# 08_Target_Bd_Connector.net
KiCad netlist of a schematic drawn in Altium Designer
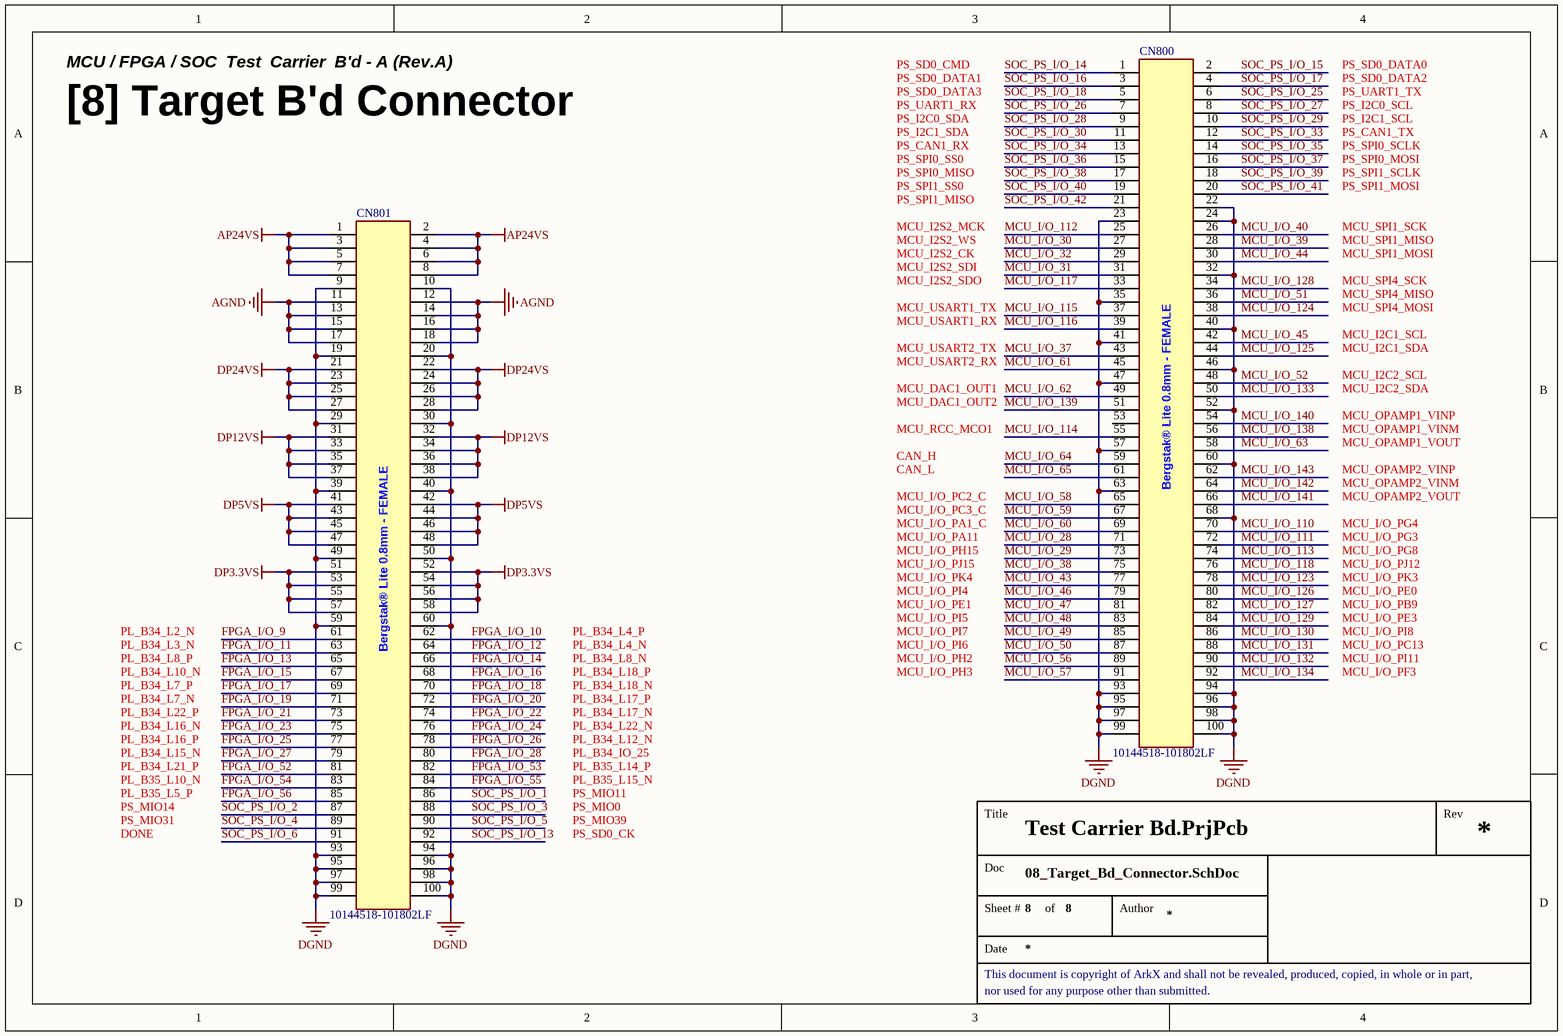
[diagram p0: 08_Target_Bd_Connector.SchDoc]

(export (version "E")
  (design (tool "Eeschema 10.0.6"))
  (components
    (comp (ref "CN800")
      (value "10144518-101802LF")
      (footprint "CON_BergStak-Lite(0.8mm)_FEMALE-100P(10144518-101802LF)_HandSolder")
      (libsource (lib "Arkx") (part "CON_BergStak-Lite(0.8mm)_FEMALE-100P(10144518-101802LF)"))
    )
    (comp (ref "CN801")
      (value "10144518-101802LF")
      (footprint "CON_BergStak-Lite(0.8mm)_FEMALE-100P(10144518-101802LF)_HandSolder")
      (libsource (lib "Arkx") (part "CON_BergStak-Lite(0.8mm)_FEMALE-100P(10144518-101802LF)"))
    )
  )
  (nets
    (net (code "1") (name "/FPGA_I{slash}O_9") (class "Default")
      (node (ref "CN801") (pin "61") (pinfunction "61_61") (pintype "passive"))
    )
    (net (code "2") (name "/FPGA_I{slash}O_10") (class "Default")
      (node (ref "CN801") (pin "62") (pinfunction "62_62") (pintype "passive"))
    )
    (net (code "3") (name "/FPGA_I{slash}O_11") (class "Default")
      (node (ref "CN801") (pin "63") (pinfunction "63_63") (pintype "passive"))
    )
    (net (code "4") (name "/FPGA_I{slash}O_12") (class "Default")
      (node (ref "CN801") (pin "64") (pinfunction "64_64") (pintype "passive"))
    )
    (net (code "5") (name "/FPGA_I{slash}O_13") (class "Default")
      (node (ref "CN801") (pin "65") (pinfunction "65_65") (pintype "passive"))
    )
    (net (code "6") (name "/FPGA_I{slash}O_14") (class "Default")
      (node (ref "CN801") (pin "66") (pinfunction "66_66") (pintype "passive"))
    )
    (net (code "7") (name "/FPGA_I{slash}O_15") (class "Default")
      (node (ref "CN801") (pin "67") (pinfunction "67_67") (pintype "passive"))
    )
    (net (code "8") (name "/FPGA_I{slash}O_16") (class "Default")
      (node (ref "CN801") (pin "68") (pinfunction "68_68") (pintype "passive"))
    )
    (net (code "9") (name "/FPGA_I{slash}O_17") (class "Default")
      (node (ref "CN801") (pin "69") (pinfunction "69_69") (pintype "passive"))
    )
    (net (code "10") (name "/FPGA_I{slash}O_18") (class "Default")
      (node (ref "CN801") (pin "70") (pinfunction "70_70") (pintype "passive"))
    )
    (net (code "11") (name "/FPGA_I{slash}O_19") (class "Default")
      (node (ref "CN801") (pin "71") (pinfunction "71_71") (pintype "passive"))
    )
    (net (code "12") (name "/FPGA_I{slash}O_20") (class "Default")
      (node (ref "CN801") (pin "72") (pinfunction "72_72") (pintype "passive"))
    )
    (net (code "13") (name "/FPGA_I{slash}O_21") (class "Default")
      (node (ref "CN801") (pin "73") (pinfunction "73_73") (pintype "passive"))
    )
    (net (code "14") (name "/FPGA_I{slash}O_22") (class "Default")
      (node (ref "CN801") (pin "74") (pinfunction "74_74") (pintype "passive"))
    )
    (net (code "15") (name "/FPGA_I{slash}O_23") (class "Default")
      (node (ref "CN801") (pin "75") (pinfunction "75_75") (pintype "passive"))
    )
    (net (code "16") (name "/FPGA_I{slash}O_24") (class "Default")
      (node (ref "CN801") (pin "76") (pinfunction "76_76") (pintype "passive"))
    )
    (net (code "17") (name "/FPGA_I{slash}O_25") (class "Default")
      (node (ref "CN801") (pin "77") (pinfunction "77_77") (pintype "passive"))
    )
    (net (code "18") (name "/FPGA_I{slash}O_26") (class "Default")
      (node (ref "CN801") (pin "78") (pinfunction "78_78") (pintype "passive"))
    )
    (net (code "19") (name "/FPGA_I{slash}O_27") (class "Default")
      (node (ref "CN801") (pin "79") (pinfunction "79_79") (pintype "passive"))
    )
    (net (code "20") (name "/FPGA_I{slash}O_28") (class "Default")
      (node (ref "CN801") (pin "80") (pinfunction "80_80") (pintype "passive"))
    )
    (net (code "21") (name "/FPGA_I{slash}O_52") (class "Default")
      (node (ref "CN801") (pin "81") (pinfunction "81_81") (pintype "passive"))
    )
    (net (code "22") (name "/FPGA_I{slash}O_53") (class "Default")
      (node (ref "CN801") (pin "82") (pinfunction "82_82") (pintype "passive"))
    )
    (net (code "23") (name "/FPGA_I{slash}O_54") (class "Default")
      (node (ref "CN801") (pin "83") (pinfunction "83_83") (pintype "passive"))
    )
    (net (code "24") (name "/FPGA_I{slash}O_55") (class "Default")
      (node (ref "CN801") (pin "84") (pinfunction "84_84") (pintype "passive"))
    )
    (net (code "25") (name "/FPGA_I{slash}O_56") (class "Default")
      (node (ref "CN801") (pin "85") (pinfunction "85_85") (pintype "passive"))
    )
    (net (code "26") (name "/MCU_I{slash}O_28") (class "Default")
      (node (ref "CN800") (pin "71") (pinfunction "71_71") (pintype "passive"))
    )
    (net (code "27") (name "/MCU_I{slash}O_29") (class "Default")
      (node (ref "CN800") (pin "73") (pinfunction "73_73") (pintype "passive"))
    )
    (net (code "28") (name "/MCU_I{slash}O_30") (class "Default")
      (node (ref "CN800") (pin "27") (pinfunction "27_27") (pintype "passive"))
    )
    (net (code "29") (name "/MCU_I{slash}O_31") (class "Default")
      (node (ref "CN800") (pin "31") (pinfunction "31_31") (pintype "passive"))
    )
    (net (code "30") (name "/MCU_I{slash}O_32") (class "Default")
      (node (ref "CN800") (pin "29") (pinfunction "29_29") (pintype "passive"))
    )
    (net (code "31") (name "/MCU_I{slash}O_37") (class "Default")
      (node (ref "CN800") (pin "43") (pinfunction "43_43") (pintype "passive"))
    )
    (net (code "32") (name "/MCU_I{slash}O_38") (class "Default")
      (node (ref "CN800") (pin "75") (pinfunction "75_75") (pintype "passive"))
    )
    (net (code "33") (name "/MCU_I{slash}O_39") (class "Default")
      (node (ref "CN800") (pin "28") (pinfunction "28_28") (pintype "passive"))
    )
    (net (code "34") (name "/MCU_I{slash}O_40") (class "Default")
      (node (ref "CN800") (pin "26") (pinfunction "26_26") (pintype "passive"))
    )
    (net (code "35") (name "/MCU_I{slash}O_43") (class "Default")
      (node (ref "CN800") (pin "77") (pinfunction "77_77") (pintype "passive"))
    )
    (net (code "36") (name "/MCU_I{slash}O_44") (class "Default")
      (node (ref "CN800") (pin "30") (pinfunction "30_30") (pintype "passive"))
    )
    (net (code "37") (name "/MCU_I{slash}O_45") (class "Default")
      (node (ref "CN800") (pin "42") (pinfunction "42_42") (pintype "passive"))
    )
    (net (code "38") (name "/MCU_I{slash}O_46") (class "Default")
      (node (ref "CN800") (pin "79") (pinfunction "79_79") (pintype "passive"))
    )
    (net (code "39") (name "/MCU_I{slash}O_47") (class "Default")
      (node (ref "CN800") (pin "81") (pinfunction "81_81") (pintype "passive"))
    )
    (net (code "40") (name "/MCU_I{slash}O_48") (class "Default")
      (node (ref "CN800") (pin "83") (pinfunction "83_83") (pintype "passive"))
    )
    (net (code "41") (name "/MCU_I{slash}O_49") (class "Default")
      (node (ref "CN800") (pin "85") (pinfunction "85_85") (pintype "passive"))
    )
    (net (code "42") (name "/MCU_I{slash}O_50") (class "Default")
      (node (ref "CN800") (pin "87") (pinfunction "87_87") (pintype "passive"))
    )
    (net (code "43") (name "/MCU_I{slash}O_51") (class "Default")
      (node (ref "CN800") (pin "36") (pinfunction "36_36") (pintype "passive"))
    )
    (net (code "44") (name "/MCU_I{slash}O_52") (class "Default")
      (node (ref "CN800") (pin "48") (pinfunction "48_48") (pintype "passive"))
    )
    (net (code "45") (name "/MCU_I{slash}O_56") (class "Default")
      (node (ref "CN800") (pin "89") (pinfunction "89_89") (pintype "passive"))
    )
    (net (code "46") (name "/MCU_I{slash}O_57") (class "Default")
      (node (ref "CN800") (pin "91") (pinfunction "91_91") (pintype "passive"))
    )
    (net (code "47") (name "/MCU_I{slash}O_58") (class "Default")
      (node (ref "CN800") (pin "65") (pinfunction "65_65") (pintype "passive"))
    )
    (net (code "48") (name "/MCU_I{slash}O_59") (class "Default")
      (node (ref "CN800") (pin "67") (pinfunction "67_67") (pintype "passive"))
    )
    (net (code "49") (name "/MCU_I{slash}O_60") (class "Default")
      (node (ref "CN800") (pin "69") (pinfunction "69_69") (pintype "passive"))
    )
    (net (code "50") (name "/MCU_I{slash}O_61") (class "Default")
      (node (ref "CN800") (pin "45") (pinfunction "45_45") (pintype "passive"))
    )
    (net (code "51") (name "/MCU_I{slash}O_62") (class "Default")
      (node (ref "CN800") (pin "49") (pinfunction "49_49") (pintype "passive"))
    )
    (net (code "52") (name "/MCU_I{slash}O_63") (class "Default")
      (node (ref "CN800") (pin "58") (pinfunction "58_58") (pintype "passive"))
    )
    (net (code "53") (name "/MCU_I{slash}O_64") (class "Default")
      (node (ref "CN800") (pin "59") (pinfunction "59_59") (pintype "passive"))
    )
    (net (code "54") (name "/MCU_I{slash}O_65") (class "Default")
      (node (ref "CN800") (pin "61") (pinfunction "61_61") (pintype "passive"))
    )
    (net (code "55") (name "/MCU_I{slash}O_110") (class "Default")
      (node (ref "CN800") (pin "70") (pinfunction "70_70") (pintype "passive"))
    )
    (net (code "56") (name "/MCU_I{slash}O_111") (class "Default")
      (node (ref "CN800") (pin "72") (pinfunction "72_72") (pintype "passive"))
    )
    (net (code "57") (name "/MCU_I{slash}O_112") (class "Default")
      (node (ref "CN800") (pin "25") (pinfunction "25_25") (pintype "passive"))
    )
    (net (code "58") (name "/MCU_I{slash}O_113") (class "Default")
      (node (ref "CN800") (pin "74") (pinfunction "74_74") (pintype "passive"))
    )
    (net (code "59") (name "/MCU_I{slash}O_114") (class "Default")
      (node (ref "CN800") (pin "55") (pinfunction "55_55") (pintype "passive"))
    )
    (net (code "60") (name "/MCU_I{slash}O_115") (class "Default")
      (node (ref "CN800") (pin "37") (pinfunction "37_37") (pintype "passive"))
    )
    (net (code "61") (name "/MCU_I{slash}O_116") (class "Default")
      (node (ref "CN800") (pin "39") (pinfunction "39_39") (pintype "passive"))
    )
    (net (code "62") (name "/MCU_I{slash}O_117") (class "Default")
      (node (ref "CN800") (pin "33") (pinfunction "33_33") (pintype "passive"))
    )
    (net (code "63") (name "/MCU_I{slash}O_118") (class "Default")
      (node (ref "CN800") (pin "76") (pinfunction "76_76") (pintype "passive"))
    )
    (net (code "64") (name "/MCU_I{slash}O_123") (class "Default")
      (node (ref "CN800") (pin "78") (pinfunction "78_78") (pintype "passive"))
    )
    (net (code "65") (name "/MCU_I{slash}O_124") (class "Default")
      (node (ref "CN800") (pin "38") (pinfunction "38_38") (pintype "passive"))
    )
    (net (code "66") (name "/MCU_I{slash}O_125") (class "Default")
      (node (ref "CN800") (pin "44") (pinfunction "44_44") (pintype "passive"))
    )
    (net (code "67") (name "/MCU_I{slash}O_126") (class "Default")
      (node (ref "CN800") (pin "80") (pinfunction "80_80") (pintype "passive"))
    )
    (net (code "68") (name "/MCU_I{slash}O_127") (class "Default")
      (node (ref "CN800") (pin "82") (pinfunction "82_82") (pintype "passive"))
    )
    (net (code "69") (name "/MCU_I{slash}O_128") (class "Default")
      (node (ref "CN800") (pin "34") (pinfunction "34_34") (pintype "passive"))
    )
    (net (code "70") (name "/MCU_I{slash}O_129") (class "Default")
      (node (ref "CN800") (pin "84") (pinfunction "84_84") (pintype "passive"))
    )
    (net (code "71") (name "/MCU_I{slash}O_130") (class "Default")
      (node (ref "CN800") (pin "86") (pinfunction "86_86") (pintype "passive"))
    )
    (net (code "72") (name "/MCU_I{slash}O_131") (class "Default")
      (node (ref "CN800") (pin "88") (pinfunction "88_88") (pintype "passive"))
    )
    (net (code "73") (name "/MCU_I{slash}O_132") (class "Default")
      (node (ref "CN800") (pin "90") (pinfunction "90_90") (pintype "passive"))
    )
    (net (code "74") (name "/MCU_I{slash}O_133") (class "Default")
      (node (ref "CN800") (pin "50") (pinfunction "50_50") (pintype "passive"))
    )
    (net (code "75") (name "/MCU_I{slash}O_134") (class "Default")
      (node (ref "CN800") (pin "92") (pinfunction "92_92") (pintype "passive"))
    )
    (net (code "76") (name "/MCU_I{slash}O_138") (class "Default")
      (node (ref "CN800") (pin "56") (pinfunction "56_56") (pintype "passive"))
    )
    (net (code "77") (name "/MCU_I{slash}O_139") (class "Default")
      (node (ref "CN800") (pin "51") (pinfunction "51_51") (pintype "passive"))
    )
    (net (code "78") (name "/MCU_I{slash}O_140") (class "Default")
      (node (ref "CN800") (pin "54") (pinfunction "54_54") (pintype "passive"))
    )
    (net (code "79") (name "/MCU_I{slash}O_141") (class "Default")
      (node (ref "CN800") (pin "66") (pinfunction "66_66") (pintype "passive"))
    )
    (net (code "80") (name "/MCU_I{slash}O_142") (class "Default")
      (node (ref "CN800") (pin "64") (pinfunction "64_64") (pintype "passive"))
    )
    (net (code "81") (name "/MCU_I{slash}O_143") (class "Default")
      (node (ref "CN800") (pin "62") (pinfunction "62_62") (pintype "passive"))
    )
    (net (code "82") (name "/SOC_PS_I{slash}O_1") (class "Default")
      (node (ref "CN801") (pin "86") (pinfunction "86_86") (pintype "passive"))
    )
    (net (code "83") (name "/SOC_PS_I{slash}O_2") (class "Default")
      (node (ref "CN801") (pin "87") (pinfunction "87_87") (pintype "passive"))
    )
    (net (code "84") (name "/SOC_PS_I{slash}O_3") (class "Default")
      (node (ref "CN801") (pin "88") (pinfunction "88_88") (pintype "passive"))
    )
    (net (code "85") (name "/SOC_PS_I{slash}O_4") (class "Default")
      (node (ref "CN801") (pin "89") (pinfunction "89_89") (pintype "passive"))
    )
    (net (code "86") (name "/SOC_PS_I{slash}O_5") (class "Default")
      (node (ref "CN801") (pin "90") (pinfunction "90_90") (pintype "passive"))
    )
    (net (code "87") (name "/SOC_PS_I{slash}O_6") (class "Default")
      (node (ref "CN801") (pin "91") (pinfunction "91_91") (pintype "passive"))
    )
    (net (code "88") (name "/SOC_PS_I{slash}O_13") (class "Default")
      (node (ref "CN801") (pin "92") (pinfunction "92_92") (pintype "passive"))
    )
    (net (code "89") (name "/SOC_PS_I{slash}O_14") (class "Default")
      (node (ref "CN800") (pin "1") (pinfunction "1_1") (pintype "passive"))
    )
    (net (code "90") (name "/SOC_PS_I{slash}O_15") (class "Default")
      (node (ref "CN800") (pin "2") (pinfunction "2_2") (pintype "passive"))
    )
    (net (code "91") (name "/SOC_PS_I{slash}O_16") (class "Default")
      (node (ref "CN800") (pin "3") (pinfunction "3_3") (pintype "passive"))
    )
    (net (code "92") (name "/SOC_PS_I{slash}O_17") (class "Default")
      (node (ref "CN800") (pin "4") (pinfunction "4_4") (pintype "passive"))
    )
    (net (code "93") (name "/SOC_PS_I{slash}O_18") (class "Default")
      (node (ref "CN800") (pin "5") (pinfunction "5_5") (pintype "passive"))
    )
    (net (code "94") (name "/SOC_PS_I{slash}O_25") (class "Default")
      (node (ref "CN800") (pin "6") (pinfunction "6_6") (pintype "passive"))
    )
    (net (code "95") (name "/SOC_PS_I{slash}O_26") (class "Default")
      (node (ref "CN800") (pin "7") (pinfunction "7_7") (pintype "passive"))
    )
    (net (code "96") (name "/SOC_PS_I{slash}O_27") (class "Default")
      (node (ref "CN800") (pin "8") (pinfunction "8_8") (pintype "passive"))
    )
    (net (code "97") (name "/SOC_PS_I{slash}O_28") (class "Default")
      (node (ref "CN800") (pin "9") (pinfunction "9_9") (pintype "passive"))
    )
    (net (code "98") (name "/SOC_PS_I{slash}O_29") (class "Default")
      (node (ref "CN800") (pin "10") (pinfunction "10_10") (pintype "passive"))
    )
    (net (code "99") (name "/SOC_PS_I{slash}O_30") (class "Default")
      (node (ref "CN800") (pin "11") (pinfunction "11_11") (pintype "passive"))
    )
    (net (code "100") (name "/SOC_PS_I{slash}O_33") (class "Default")
      (node (ref "CN800") (pin "12") (pinfunction "12_12") (pintype "passive"))
    )
    (net (code "101") (name "/SOC_PS_I{slash}O_34") (class "Default")
      (node (ref "CN800") (pin "13") (pinfunction "13_13") (pintype "passive"))
    )
    (net (code "102") (name "/SOC_PS_I{slash}O_35") (class "Default")
      (node (ref "CN800") (pin "14") (pinfunction "14_14") (pintype "passive"))
    )
    (net (code "103") (name "/SOC_PS_I{slash}O_36") (class "Default")
      (node (ref "CN800") (pin "15") (pinfunction "15_15") (pintype "passive"))
    )
    (net (code "104") (name "/SOC_PS_I{slash}O_37") (class "Default")
      (node (ref "CN800") (pin "16") (pinfunction "16_16") (pintype "passive"))
    )
    (net (code "105") (name "/SOC_PS_I{slash}O_38") (class "Default")
      (node (ref "CN800") (pin "17") (pinfunction "17_17") (pintype "passive"))
    )
    (net (code "106") (name "/SOC_PS_I{slash}O_39") (class "Default")
      (node (ref "CN800") (pin "18") (pinfunction "18_18") (pintype "passive"))
    )
    (net (code "107") (name "/SOC_PS_I{slash}O_40") (class "Default")
      (node (ref "CN800") (pin "19") (pinfunction "19_19") (pintype "passive"))
    )
    (net (code "108") (name "/SOC_PS_I{slash}O_41") (class "Default")
      (node (ref "CN800") (pin "20") (pinfunction "20_20") (pintype "passive"))
    )
    (net (code "109") (name "/SOC_PS_I{slash}O_42") (class "Default")
      (node (ref "CN800") (pin "21") (pinfunction "21_21") (pintype "passive"))
    )
    (net (code "110") (name "AGND") (class "Default")
      (node (ref "CN801") (pin "11") (pinfunction "11_11") (pintype "passive"))
      (node (ref "CN801") (pin "12") (pinfunction "12_12") (pintype "passive"))
      (node (ref "CN801") (pin "13") (pinfunction "13_13") (pintype "passive"))
      (node (ref "CN801") (pin "14") (pinfunction "14_14") (pintype "passive"))
      (node (ref "CN801") (pin "15") (pinfunction "15_15") (pintype "passive"))
      (node (ref "CN801") (pin "16") (pinfunction "16_16") (pintype "passive"))
      (node (ref "CN801") (pin "17") (pinfunction "17_17") (pintype "passive"))
      (node (ref "CN801") (pin "18") (pinfunction "18_18") (pintype "passive"))
    )
    (net (code "111") (name "AP24VS") (class "Default")
      (node (ref "CN801") (pin "1") (pinfunction "1_1") (pintype "passive"))
      (node (ref "CN801") (pin "2") (pinfunction "2_2") (pintype "passive"))
      (node (ref "CN801") (pin "3") (pinfunction "3_3") (pintype "passive"))
      (node (ref "CN801") (pin "4") (pinfunction "4_4") (pintype "passive"))
      (node (ref "CN801") (pin "5") (pinfunction "5_5") (pintype "passive"))
      (node (ref "CN801") (pin "6") (pinfunction "6_6") (pintype "passive"))
      (node (ref "CN801") (pin "7") (pinfunction "7_7") (pintype "passive"))
      (node (ref "CN801") (pin "8") (pinfunction "8_8") (pintype "passive"))
    )
    (net (code "112") (name "DGND") (class "Default")
      (node (ref "CN800") (pin "100") (pinfunction "100_100") (pintype "passive"))
      (node (ref "CN800") (pin "22") (pinfunction "22_22") (pintype "passive"))
      (node (ref "CN800") (pin "23") (pinfunction "23_23") (pintype "passive"))
      (node (ref "CN800") (pin "24") (pinfunction "24_24") (pintype "passive"))
      (node (ref "CN800") (pin "32") (pinfunction "32_32") (pintype "passive"))
      (node (ref "CN800") (pin "35") (pinfunction "35_35") (pintype "passive"))
      (node (ref "CN800") (pin "40") (pinfunction "40_40") (pintype "passive"))
      (node (ref "CN800") (pin "41") (pinfunction "41_41") (pintype "passive"))
      (node (ref "CN800") (pin "46") (pinfunction "46_46") (pintype "passive"))
      (node (ref "CN800") (pin "47") (pinfunction "47_47") (pintype "passive"))
      (node (ref "CN800") (pin "52") (pinfunction "52_52") (pintype "passive"))
      (node (ref "CN800") (pin "57") (pinfunction "57_57") (pintype "passive"))
      (node (ref "CN800") (pin "60") (pinfunction "60_60") (pintype "passive"))
      (node (ref "CN800") (pin "63") (pinfunction "63_63") (pintype "passive"))
      (node (ref "CN800") (pin "68") (pinfunction "68_68") (pintype "passive"))
      (node (ref "CN800") (pin "93") (pinfunction "93_93") (pintype "passive"))
      (node (ref "CN800") (pin "94") (pinfunction "94_94") (pintype "passive"))
      (node (ref "CN800") (pin "95") (pinfunction "95_95") (pintype "passive"))
      (node (ref "CN800") (pin "96") (pinfunction "96_96") (pintype "passive"))
      (node (ref "CN800") (pin "97") (pinfunction "97_97") (pintype "passive"))
      (node (ref "CN800") (pin "98") (pinfunction "98_98") (pintype "passive"))
      (node (ref "CN800") (pin "99") (pinfunction "99_99") (pintype "passive"))
      (node (ref "CN801") (pin "10") (pinfunction "10_10") (pintype "passive"))
      (node (ref "CN801") (pin "100") (pinfunction "100_100") (pintype "passive"))
      (node (ref "CN801") (pin "19") (pinfunction "19_19") (pintype "passive"))
      (node (ref "CN801") (pin "20") (pinfunction "20_20") (pintype "passive"))
      (node (ref "CN801") (pin "29") (pinfunction "29_29") (pintype "passive"))
      (node (ref "CN801") (pin "30") (pinfunction "30_30") (pintype "passive"))
      (node (ref "CN801") (pin "39") (pinfunction "39_39") (pintype "passive"))
      (node (ref "CN801") (pin "40") (pinfunction "40_40") (pintype "passive"))
      (node (ref "CN801") (pin "49") (pinfunction "49_49") (pintype "passive"))
      (node (ref "CN801") (pin "50") (pinfunction "50_50") (pintype "passive"))
      (node (ref "CN801") (pin "59") (pinfunction "59_59") (pintype "passive"))
      (node (ref "CN801") (pin "60") (pinfunction "60_60") (pintype "passive"))
      (node (ref "CN801") (pin "9") (pinfunction "9_9") (pintype "passive"))
      (node (ref "CN801") (pin "93") (pinfunction "93_93") (pintype "passive"))
      (node (ref "CN801") (pin "94") (pinfunction "94_94") (pintype "passive"))
      (node (ref "CN801") (pin "95") (pinfunction "95_95") (pintype "passive"))
      (node (ref "CN801") (pin "96") (pinfunction "96_96") (pintype "passive"))
      (node (ref "CN801") (pin "97") (pinfunction "97_97") (pintype "passive"))
      (node (ref "CN801") (pin "98") (pinfunction "98_98") (pintype "passive"))
      (node (ref "CN801") (pin "99") (pinfunction "99_99") (pintype "passive"))
    )
    (net (code "113") (name "DP3.3VS") (class "Default")
      (node (ref "CN801") (pin "51") (pinfunction "51_51") (pintype "passive"))
      (node (ref "CN801") (pin "52") (pinfunction "52_52") (pintype "passive"))
      (node (ref "CN801") (pin "53") (pinfunction "53_53") (pintype "passive"))
      (node (ref "CN801") (pin "54") (pinfunction "54_54") (pintype "passive"))
      (node (ref "CN801") (pin "55") (pinfunction "55_55") (pintype "passive"))
      (node (ref "CN801") (pin "56") (pinfunction "56_56") (pintype "passive"))
      (node (ref "CN801") (pin "57") (pinfunction "57_57") (pintype "passive"))
      (node (ref "CN801") (pin "58") (pinfunction "58_58") (pintype "passive"))
    )
    (net (code "114") (name "DP5VS") (class "Default")
      (node (ref "CN801") (pin "41") (pinfunction "41_41") (pintype "passive"))
      (node (ref "CN801") (pin "42") (pinfunction "42_42") (pintype "passive"))
      (node (ref "CN801") (pin "43") (pinfunction "43_43") (pintype "passive"))
      (node (ref "CN801") (pin "44") (pinfunction "44_44") (pintype "passive"))
      (node (ref "CN801") (pin "45") (pinfunction "45_45") (pintype "passive"))
      (node (ref "CN801") (pin "46") (pinfunction "46_46") (pintype "passive"))
      (node (ref "CN801") (pin "47") (pinfunction "47_47") (pintype "passive"))
      (node (ref "CN801") (pin "48") (pinfunction "48_48") (pintype "passive"))
    )
    (net (code "115") (name "DP12VS") (class "Default")
      (node (ref "CN801") (pin "31") (pinfunction "31_31") (pintype "passive"))
      (node (ref "CN801") (pin "32") (pinfunction "32_32") (pintype "passive"))
      (node (ref "CN801") (pin "33") (pinfunction "33_33") (pintype "passive"))
      (node (ref "CN801") (pin "34") (pinfunction "34_34") (pintype "passive"))
      (node (ref "CN801") (pin "35") (pinfunction "35_35") (pintype "passive"))
      (node (ref "CN801") (pin "36") (pinfunction "36_36") (pintype "passive"))
      (node (ref "CN801") (pin "37") (pinfunction "37_37") (pintype "passive"))
      (node (ref "CN801") (pin "38") (pinfunction "38_38") (pintype "passive"))
    )
    (net (code "116") (name "DP24VS") (class "Default")
      (node (ref "CN801") (pin "21") (pinfunction "21_21") (pintype "passive"))
      (node (ref "CN801") (pin "22") (pinfunction "22_22") (pintype "passive"))
      (node (ref "CN801") (pin "23") (pinfunction "23_23") (pintype "passive"))
      (node (ref "CN801") (pin "24") (pinfunction "24_24") (pintype "passive"))
      (node (ref "CN801") (pin "25") (pinfunction "25_25") (pintype "passive"))
      (node (ref "CN801") (pin "26") (pinfunction "26_26") (pintype "passive"))
      (node (ref "CN801") (pin "27") (pinfunction "27_27") (pintype "passive"))
      (node (ref "CN801") (pin "28") (pinfunction "28_28") (pintype "passive"))
    )
    (net (code "117") (name "unconnected-(CN800-Pad53)") (class "Default")
      (node (ref "CN800") (pin "53") (pinfunction "53_53") (pintype "passive"))
    )
  )
)
